# LoudnessControl.net
KiCad netlist of a schematic drawn in Altium Designer
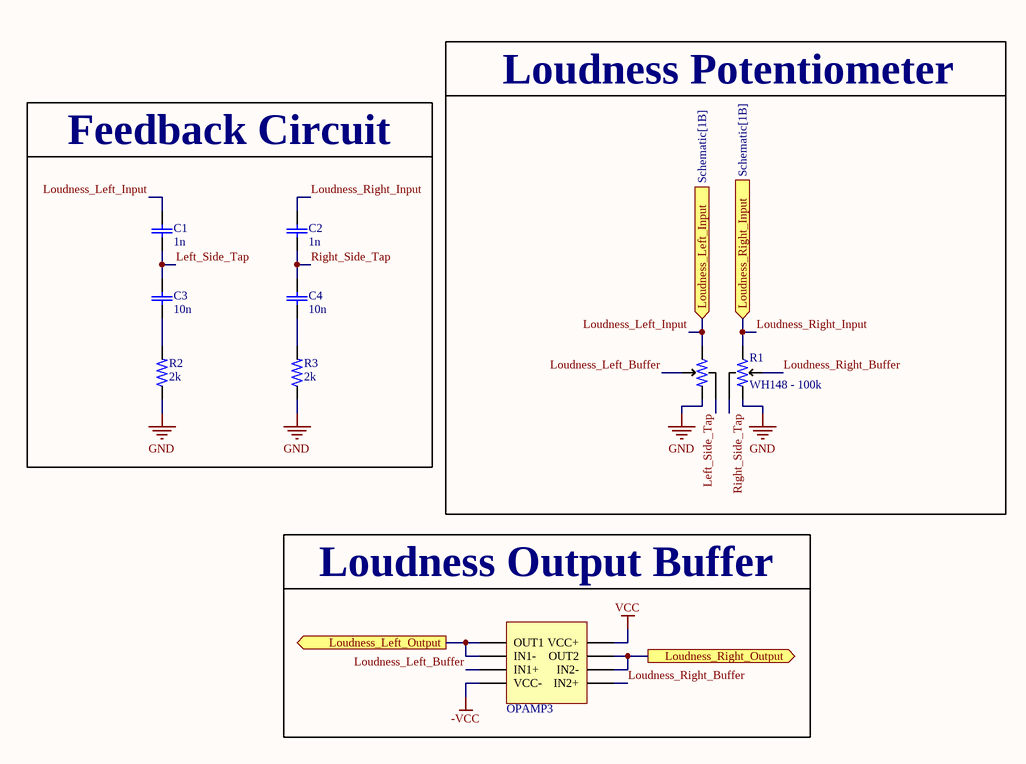
[diagram p0: LoudnessControl.SchDoc]

(export (version "E")
  (design (tool "Eeschema 10.0.6"))
  (components
    (comp (ref "C1")
      (value "1n")
      (footprint "CERAMIC0603")
      (fields (field (name "MF") "KEMET") (field (name "MP") "TAJC226M025RNJ"))
      (libsource (lib "AltiumLibrary-Mugetsu") (part "Cap"))
    )
    (comp (ref "C2")
      (value "1n")
      (footprint "CERAMIC0603")
      (fields (field (name "MF") "KEMET") (field (name "MP") "TAJC226M025RNJ"))
      (libsource (lib "AltiumLibrary-Mugetsu") (part "Cap"))
    )
    (comp (ref "C3")
      (value "10n")
      (footprint "CERAMIC0603")
      (fields (field (name "MF") "KEMET") (field (name "MP") "TAJC226M025RNJ"))
      (libsource (lib "AltiumLibrary-Mugetsu") (part "Cap"))
    )
    (comp (ref "C4")
      (value "10n")
      (footprint "CERAMIC0603")
      (fields (field (name "MF") "KEMET") (field (name "MP") "TAJC226M025RNJ"))
      (libsource (lib "AltiumLibrary-Mugetsu") (part "Cap"))
    )
    (comp (ref "OPAMP3")
      (value "TL072")
      (footprint "DIP8")
      (libsource (lib "AltiumLibrary-Mugetsu") (part "TL072"))
    )
    (comp (ref "R1")
      (value "WH148 - 100k")
      (footprint "WH148")
      (libsource (lib "AltiumLibrary-Mugetsu") (part "WH148"))
    )
    (comp (ref "R2")
      (value "2k")
      (footprint "RES0603")
      (fields (field (name "MP") "3-1879460-6"))
      (libsource (lib "AltiumLibrary-Mugetsu") (part "RESISTOR SMD"))
    )
    (comp (ref "R3")
      (value "2k")
      (footprint "RES0603")
      (fields (field (name "MP") "3-1879460-6"))
      (libsource (lib "AltiumLibrary-Mugetsu") (part "RESISTOR SMD"))
    )
  )
  (nets
    (net (code "1") (name "-VCC") (class "Default")
      (node (ref "OPAMP3") (pin "4") (pinfunction "VCC-_4") (pintype "passive"))
    )
    (net (code "2") (name "/Left_Side_Tap") (class "Default")
      (node (ref "C1") (pin "1") (pinfunction "C1_1") (pintype "passive"))
      (node (ref "C3") (pin "2") (pinfunction "C2_2") (pintype "passive"))
      (node (ref "R1") (pin "8") (pinfunction "8_8") (pintype "passive"))
    )
    (net (code "3") (name "/Loudness_Left_Buffer") (class "Default")
      (node (ref "OPAMP3") (pin "3") (pinfunction "IN1+_3") (pintype "passive"))
      (node (ref "R1") (pin "6") (pinfunction "6_6") (pintype "passive"))
    )
    (net (code "4") (name "/Loudness_Left_Input") (class "Default")
      (node (ref "C1") (pin "2") (pinfunction "C2_2") (pintype "passive"))
      (node (ref "R1") (pin "5") (pinfunction "5_5") (pintype "passive"))
    )
    (net (code "5") (name "/Loudness_Left_Output") (class "Default")
      (node (ref "OPAMP3") (pin "1") (pinfunction "OUT1_1") (pintype "passive"))
      (node (ref "OPAMP3") (pin "2") (pinfunction "IN1-_2") (pintype "passive"))
    )
    (net (code "6") (name "/Loudness_Right_Buffer") (class "Default")
      (node (ref "OPAMP3") (pin "5") (pinfunction "IN2+_5") (pintype "passive"))
      (node (ref "R1") (pin "2") (pinfunction "2_2") (pintype "passive"))
    )
    (net (code "7") (name "/Loudness_Right_Input") (class "Default")
      (node (ref "C2") (pin "2") (pinfunction "C2_2") (pintype "passive"))
      (node (ref "R1") (pin "1") (pinfunction "1_1") (pintype "passive"))
    )
    (net (code "8") (name "/Loudness_Right_Output") (class "Default")
      (node (ref "OPAMP3") (pin "6") (pinfunction "IN2-_6") (pintype "passive"))
      (node (ref "OPAMP3") (pin "7") (pinfunction "OUT2_7") (pintype "passive"))
    )
    (net (code "9") (name "/Right_Side_Tap") (class "Default")
      (node (ref "C2") (pin "1") (pinfunction "C1_1") (pintype "passive"))
      (node (ref "C4") (pin "2") (pinfunction "C2_2") (pintype "passive"))
      (node (ref "R1") (pin "4") (pinfunction "4_4") (pintype "passive"))
    )
    (net (code "10") (name "GND") (class "Default")
      (node (ref "R1") (pin "3") (pinfunction "3_3") (pintype "passive"))
      (node (ref "R1") (pin "7") (pinfunction "7_7") (pintype "passive"))
      (node (ref "R2") (pin "1") (pinfunction "1_1") (pintype "passive"))
      (node (ref "R3") (pin "1") (pinfunction "1_1") (pintype "passive"))
    )
    (net (code "11") (name "Net-(C3-C1)") (class "Default")
      (node (ref "C3") (pin "1") (pinfunction "C1_1") (pintype "passive"))
      (node (ref "R2") (pin "2") (pinfunction "2_2") (pintype "passive"))
    )
    (net (code "12") (name "Net-(C4-C1)") (class "Default")
      (node (ref "C4") (pin "1") (pinfunction "C1_1") (pintype "passive"))
      (node (ref "R3") (pin "2") (pinfunction "2_2") (pintype "passive"))
    )
    (net (code "13") (name "VCC") (class "Default")
      (node (ref "OPAMP3") (pin "8") (pinfunction "VCC+_8") (pintype "passive"))
    )
  )
)
